# LCD_VGA.net
KiCad netlist of a schematic drawn in Altium Designer
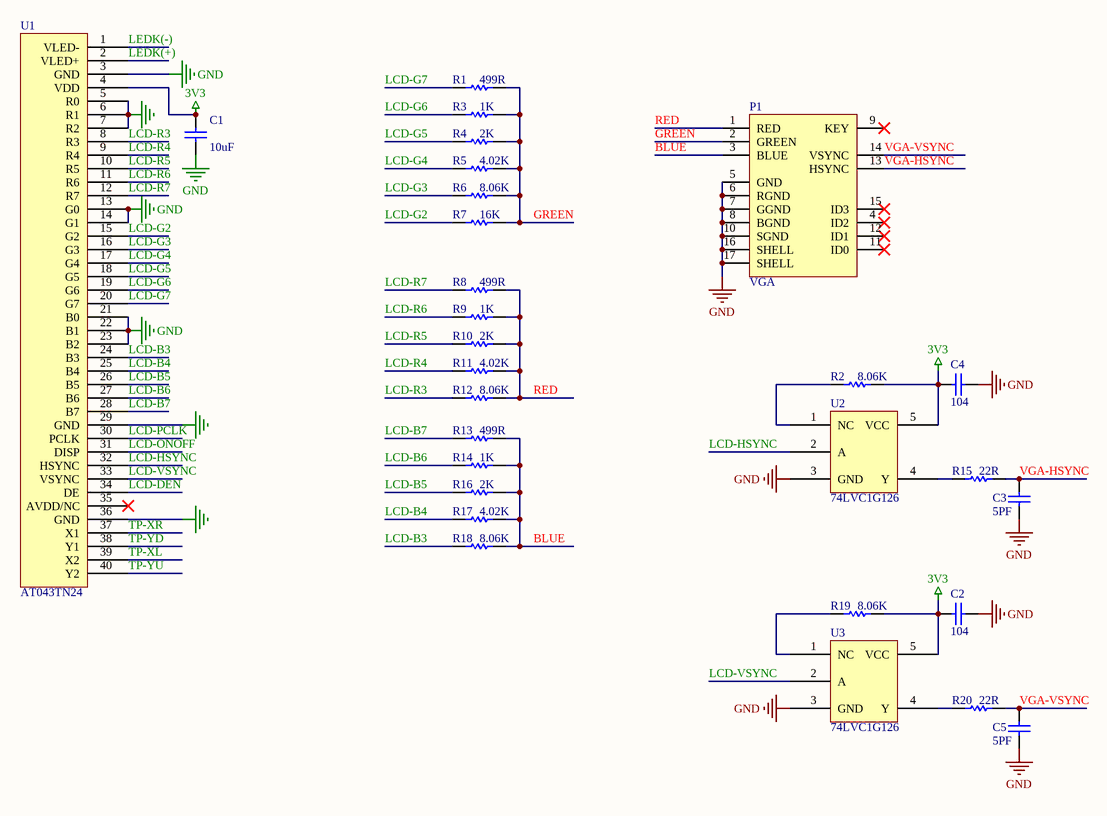
[diagram p0: LCD_VGA.SchDoc]

(export (version "E")
  (design (tool "Eeschema 10.0.6"))
  (components
    (comp (ref "C1")
      (value "C10uF")
      (footprint "0603C")
      (fields (field (name "ALTIUM_UNNAMED_1") "10uF"))
      (libsource (lib "OKmeSchLibrary") (part "C10uF-B"))
    )
    (comp (ref "C2")
      (value "104")
      (footprint "0603C")
      (fields (field (name "ALTIUM_UNNAMED_1") "104"))
      (libsource (lib "OKmeSchLibrary") (part "C10uF-B"))
    )
    (comp (ref "C3")
      (value "5PF")
      (footprint "0603C")
      (fields (field (name "ALTIUM_UNNAMED_1") "5PF"))
      (libsource (lib "OKmeSchLibrary") (part "C10uF-B"))
    )
    (comp (ref "C4")
      (value "104")
      (footprint "0603C")
      (fields (field (name "ALTIUM_UNNAMED_1") "104"))
      (libsource (lib "OKmeSchLibrary") (part "C10uF-B"))
    )
    (comp (ref "C5")
      (value "5PF")
      (footprint "0603C")
      (fields (field (name "ALTIUM_UNNAMED_1") "5PF"))
      (libsource (lib "OKmeSchLibrary") (part "C10uF-B"))
    )
    (comp (ref "P1") (value "VGA") (footprint "VGA-DB15") (libsource (lib "osc_dev") (part "VGA")))
    (comp (ref "R1")
      (value "499R")
      (footprint "0603R")
      (fields (field (name "ALTIUM_UNNAMED_1") "499R"))
      (libsource (lib "OKmeSchLibrary") (part "R1M"))
    )
    (comp (ref "R2")
      (value "8.06K")
      (footprint "0603R")
      (fields (field (name "ALTIUM_UNNAMED_1") "8.06K"))
      (libsource (lib "OKmeSchLibrary") (part "R1M"))
    )
    (comp (ref "R3")
      (value "1K")
      (footprint "0603R")
      (fields (field (name "ALTIUM_UNNAMED_1") "1K"))
      (libsource (lib "OKmeSchLibrary") (part "R1M"))
    )
    (comp (ref "R4")
      (value "2K")
      (footprint "0603R")
      (fields (field (name "ALTIUM_UNNAMED_1") "2K"))
      (libsource (lib "OKmeSchLibrary") (part "R1M"))
    )
    (comp (ref "R5")
      (value "4.02K")
      (footprint "0603R")
      (fields (field (name "ALTIUM_UNNAMED_1") "4.02K"))
      (libsource (lib "OKmeSchLibrary") (part "R1M"))
    )
    (comp (ref "R6")
      (value "8.06K")
      (footprint "0603R")
      (fields (field (name "ALTIUM_UNNAMED_1") "8.06K"))
      (libsource (lib "OKmeSchLibrary") (part "R1M"))
    )
    (comp (ref "R7")
      (value "16K")
      (footprint "0603R")
      (fields (field (name "ALTIUM_UNNAMED_1") "16K"))
      (libsource (lib "OKmeSchLibrary") (part "R1M"))
    )
    (comp (ref "R8")
      (value "499R")
      (footprint "0603R")
      (fields (field (name "ALTIUM_UNNAMED_1") "499R"))
      (libsource (lib "OKmeSchLibrary") (part "R1M"))
    )
    (comp (ref "R9")
      (value "1K")
      (footprint "0603R")
      (fields (field (name "ALTIUM_UNNAMED_1") "1K"))
      (libsource (lib "OKmeSchLibrary") (part "R1M"))
    )
    (comp (ref "R10")
      (value "2K")
      (footprint "0603R")
      (fields (field (name "ALTIUM_UNNAMED_1") "2K"))
      (libsource (lib "OKmeSchLibrary") (part "R1M"))
    )
    (comp (ref "R11")
      (value "4.02K")
      (footprint "0603R")
      (fields (field (name "ALTIUM_UNNAMED_1") "4.02K"))
      (libsource (lib "OKmeSchLibrary") (part "R1M"))
    )
    (comp (ref "R12")
      (value "8.06K")
      (footprint "0603R")
      (fields (field (name "ALTIUM_UNNAMED_1") "8.06K"))
      (libsource (lib "OKmeSchLibrary") (part "R1M"))
    )
    (comp (ref "R13")
      (value "499R")
      (footprint "0603R")
      (fields (field (name "ALTIUM_UNNAMED_1") "499R"))
      (libsource (lib "OKmeSchLibrary") (part "R1M"))
    )
    (comp (ref "R14")
      (value "1K")
      (footprint "0603R")
      (fields (field (name "ALTIUM_UNNAMED_1") "1K"))
      (libsource (lib "OKmeSchLibrary") (part "R1M"))
    )
    (comp (ref "R15")
      (value "22R")
      (footprint "0603R")
      (fields (field (name "ALTIUM_UNNAMED_1") "22R"))
      (libsource (lib "OKmeSchLibrary") (part "R1M"))
    )
    (comp (ref "R16")
      (value "2K")
      (footprint "0603R")
      (fields (field (name "ALTIUM_UNNAMED_1") "2K"))
      (libsource (lib "OKmeSchLibrary") (part "R1M"))
    )
    (comp (ref "R17")
      (value "4.02K")
      (footprint "0603R")
      (fields (field (name "ALTIUM_UNNAMED_1") "4.02K"))
      (libsource (lib "OKmeSchLibrary") (part "R1M"))
    )
    (comp (ref "R18")
      (value "8.06K")
      (footprint "0603R")
      (fields (field (name "ALTIUM_UNNAMED_1") "8.06K"))
      (libsource (lib "OKmeSchLibrary") (part "R1M"))
    )
    (comp (ref "R19")
      (value "8.06K")
      (footprint "0603R")
      (fields (field (name "ALTIUM_UNNAMED_1") "8.06K"))
      (libsource (lib "OKmeSchLibrary") (part "R1M"))
    )
    (comp (ref "R20")
      (value "22R")
      (footprint "0603R")
      (fields (field (name "ALTIUM_UNNAMED_1") "22R"))
      (libsource (lib "OKmeSchLibrary") (part "R1M"))
    )
    (comp (ref "U1")
      (value "AT043TN24")
      (footprint "FPC40-N")
      (libsource (lib "OKmeSchLibrary") (part "AT043TN24"))
    )
    (comp (ref "U2")
      (value "74LVC1G126")
      (footprint "SOT23-5")
      (libsource (lib "OKmeSchLibrary") (part "74LVC1G17"))
    )
    (comp (ref "U3")
      (value "74LVC1G126")
      (footprint "SOT23-5")
      (libsource (lib "OKmeSchLibrary") (part "74LVC1G17"))
    )
  )
  (nets
    (net (code "1") (name "/BLUE") (class "Default")
      (node (ref "P1") (pin "3") (pinfunction "BLUE_3") (pintype "passive"))
      (node (ref "R13") (pin "1") (pinfunction "1_1") (pintype "passive"))
      (node (ref "R14") (pin "1") (pinfunction "1_1") (pintype "passive"))
      (node (ref "R16") (pin "1") (pinfunction "1_1") (pintype "passive"))
      (node (ref "R17") (pin "1") (pinfunction "1_1") (pintype "passive"))
      (node (ref "R18") (pin "1") (pinfunction "1_1") (pintype "passive"))
    )
    (net (code "2") (name "/GREEN") (class "Default")
      (node (ref "P1") (pin "2") (pinfunction "GREEN_2") (pintype "passive"))
      (node (ref "R1") (pin "1") (pinfunction "1_1") (pintype "passive"))
      (node (ref "R3") (pin "1") (pinfunction "1_1") (pintype "passive"))
      (node (ref "R4") (pin "1") (pinfunction "1_1") (pintype "passive"))
      (node (ref "R5") (pin "1") (pinfunction "1_1") (pintype "passive"))
      (node (ref "R6") (pin "1") (pinfunction "1_1") (pintype "passive"))
      (node (ref "R7") (pin "1") (pinfunction "1_1") (pintype "passive"))
    )
    (net (code "3") (name "/LCD-B3") (class "Default")
      (node (ref "R18") (pin "2") (pinfunction "2_2") (pintype "passive"))
      (node (ref "U1") (pin "24") (pinfunction "B3_24") (pintype "passive"))
    )
    (net (code "4") (name "/LCD-B4") (class "Default")
      (node (ref "R17") (pin "2") (pinfunction "2_2") (pintype "passive"))
      (node (ref "U1") (pin "25") (pinfunction "B4_25") (pintype "passive"))
    )
    (net (code "5") (name "/LCD-B5") (class "Default")
      (node (ref "R16") (pin "2") (pinfunction "2_2") (pintype "passive"))
      (node (ref "U1") (pin "26") (pinfunction "B5_26") (pintype "passive"))
    )
    (net (code "6") (name "/LCD-B6") (class "Default")
      (node (ref "R14") (pin "2") (pinfunction "2_2") (pintype "passive"))
      (node (ref "U1") (pin "27") (pinfunction "B6_27") (pintype "passive"))
    )
    (net (code "7") (name "/LCD-B7") (class "Default")
      (node (ref "R13") (pin "2") (pinfunction "2_2") (pintype "passive"))
      (node (ref "U1") (pin "28") (pinfunction "B7_28") (pintype "passive"))
    )
    (net (code "8") (name "/LCD-DEN") (class "Default")
      (node (ref "U1") (pin "34") (pinfunction "DE_34") (pintype "passive"))
    )
    (net (code "9") (name "/LCD-G2") (class "Default")
      (node (ref "R7") (pin "2") (pinfunction "2_2") (pintype "passive"))
      (node (ref "U1") (pin "15") (pinfunction "G2_15") (pintype "passive"))
    )
    (net (code "10") (name "/LCD-G3") (class "Default")
      (node (ref "R6") (pin "2") (pinfunction "2_2") (pintype "passive"))
      (node (ref "U1") (pin "16") (pinfunction "G3_16") (pintype "passive"))
    )
    (net (code "11") (name "/LCD-G4") (class "Default")
      (node (ref "R5") (pin "2") (pinfunction "2_2") (pintype "passive"))
      (node (ref "U1") (pin "17") (pinfunction "G4_17") (pintype "passive"))
    )
    (net (code "12") (name "/LCD-G5") (class "Default")
      (node (ref "R4") (pin "2") (pinfunction "2_2") (pintype "passive"))
      (node (ref "U1") (pin "18") (pinfunction "G5_18") (pintype "passive"))
    )
    (net (code "13") (name "/LCD-G6") (class "Default")
      (node (ref "R3") (pin "2") (pinfunction "2_2") (pintype "passive"))
      (node (ref "U1") (pin "19") (pinfunction "G6_19") (pintype "passive"))
    )
    (net (code "14") (name "/LCD-G7") (class "Default")
      (node (ref "R1") (pin "2") (pinfunction "2_2") (pintype "passive"))
      (node (ref "U1") (pin "20") (pinfunction "G7_20") (pintype "passive"))
    )
    (net (code "15") (name "/LCD-HSYNC") (class "Default")
      (node (ref "U1") (pin "32") (pinfunction "HSYNC_32") (pintype "passive"))
      (node (ref "U2") (pin "2") (pinfunction "A_2") (pintype "passive"))
    )
    (net (code "16") (name "/LCD-ONOFF") (class "Default")
      (node (ref "U1") (pin "31") (pinfunction "DISP_31") (pintype "passive"))
    )
    (net (code "17") (name "/LCD-PCLK") (class "Default")
      (node (ref "U1") (pin "30") (pinfunction "PCLK_30") (pintype "passive"))
    )
    (net (code "18") (name "/LCD-R3") (class "Default")
      (node (ref "R12") (pin "2") (pinfunction "2_2") (pintype "passive"))
      (node (ref "U1") (pin "8") (pinfunction "R3_8") (pintype "passive"))
    )
    (net (code "19") (name "/LCD-R4") (class "Default")
      (node (ref "R11") (pin "2") (pinfunction "2_2") (pintype "passive"))
      (node (ref "U1") (pin "9") (pinfunction "R4_9") (pintype "passive"))
    )
    (net (code "20") (name "/LCD-R5") (class "Default")
      (node (ref "R10") (pin "2") (pinfunction "2_2") (pintype "passive"))
      (node (ref "U1") (pin "10") (pinfunction "R5_10") (pintype "passive"))
    )
    (net (code "21") (name "/LCD-R6") (class "Default")
      (node (ref "R9") (pin "2") (pinfunction "2_2") (pintype "passive"))
      (node (ref "U1") (pin "11") (pinfunction "R6_11") (pintype "passive"))
    )
    (net (code "22") (name "/LCD-R7") (class "Default")
      (node (ref "R8") (pin "2") (pinfunction "2_2") (pintype "passive"))
      (node (ref "U1") (pin "12") (pinfunction "R7_12") (pintype "passive"))
    )
    (net (code "23") (name "/LCD-VSYNC") (class "Default")
      (node (ref "U1") (pin "33") (pinfunction "VSYNC_33") (pintype "passive"))
      (node (ref "U3") (pin "2") (pinfunction "A_2") (pintype "passive"))
    )
    (net (code "24") (name "/LEDK(+)") (class "Default")
      (node (ref "U1") (pin "2") (pinfunction "VLED+_2") (pintype "passive"))
    )
    (net (code "25") (name "/LEDK(-)") (class "Default")
      (node (ref "U1") (pin "1") (pinfunction "VLED-_1") (pintype "passive"))
    )
    (net (code "26") (name "/RED") (class "Default")
      (node (ref "P1") (pin "1") (pinfunction "RED_1") (pintype "passive"))
      (node (ref "R10") (pin "1") (pinfunction "1_1") (pintype "passive"))
      (node (ref "R11") (pin "1") (pinfunction "1_1") (pintype "passive"))
      (node (ref "R12") (pin "1") (pinfunction "1_1") (pintype "passive"))
      (node (ref "R8") (pin "1") (pinfunction "1_1") (pintype "passive"))
      (node (ref "R9") (pin "1") (pinfunction "1_1") (pintype "passive"))
    )
    (net (code "27") (name "/TP-XL") (class "Default")
      (node (ref "U1") (pin "39") (pinfunction "X2_39") (pintype "passive"))
    )
    (net (code "28") (name "/TP-XR") (class "Default")
      (node (ref "U1") (pin "37") (pinfunction "X1_37") (pintype "passive"))
    )
    (net (code "29") (name "/TP-YD") (class "Default")
      (node (ref "U1") (pin "38") (pinfunction "Y1_38") (pintype "passive"))
    )
    (net (code "30") (name "/TP-YU") (class "Default")
      (node (ref "U1") (pin "40") (pinfunction "Y2_40") (pintype "passive"))
    )
    (net (code "31") (name "/VGA-HSYNC") (class "Default")
      (node (ref "C3") (pin "1") (pinfunction "1_1") (pintype "passive"))
      (node (ref "P1") (pin "13") (pinfunction "HSYNC_13") (pintype "passive"))
      (node (ref "R15") (pin "1") (pinfunction "1_1") (pintype "passive"))
    )
    (net (code "32") (name "/VGA-VSYNC") (class "Default")
      (node (ref "C5") (pin "1") (pinfunction "1_1") (pintype "passive"))
      (node (ref "P1") (pin "14") (pinfunction "VSYNC_14") (pintype "passive"))
      (node (ref "R20") (pin "1") (pinfunction "1_1") (pintype "passive"))
    )
    (net (code "33") (name "3V3") (class "Default")
      (node (ref "C1") (pin "1") (pinfunction "1_1") (pintype "passive"))
      (node (ref "C2") (pin "2") (pinfunction "2_2") (pintype "passive"))
      (node (ref "C4") (pin "2") (pinfunction "2_2") (pintype "passive"))
      (node (ref "R19") (pin "1") (pinfunction "1_1") (pintype "passive"))
      (node (ref "R2") (pin "1") (pinfunction "1_1") (pintype "passive"))
      (node (ref "U1") (pin "4") (pinfunction "VDD_4") (pintype "passive"))
      (node (ref "U2") (pin "5") (pinfunction "VCC_5") (pintype "passive"))
      (node (ref "U3") (pin "5") (pinfunction "VCC_5") (pintype "passive"))
    )
    (net (code "34") (name "GND") (class "Default")
      (node (ref "C1") (pin "2") (pinfunction "2_2") (pintype "passive"))
      (node (ref "C2") (pin "1") (pinfunction "1_1") (pintype "passive"))
      (node (ref "C3") (pin "2") (pinfunction "2_2") (pintype "passive"))
      (node (ref "C4") (pin "1") (pinfunction "1_1") (pintype "passive"))
      (node (ref "C5") (pin "2") (pinfunction "2_2") (pintype "passive"))
      (node (ref "P1") (pin "10") (pinfunction "SGND_10") (pintype "passive"))
      (node (ref "P1") (pin "16") (pinfunction "SHELL_16") (pintype "passive"))
      (node (ref "P1") (pin "17") (pinfunction "SHELL_17") (pintype "passive"))
      (node (ref "P1") (pin "5") (pinfunction "GND_5") (pintype "passive"))
      (node (ref "P1") (pin "6") (pinfunction "RGND_6") (pintype "passive"))
      (node (ref "P1") (pin "7") (pinfunction "GGND_7") (pintype "passive"))
      (node (ref "P1") (pin "8") (pinfunction "BGND_8") (pintype "passive"))
      (node (ref "U1") (pin "13") (pinfunction "G0_13") (pintype "passive"))
      (node (ref "U1") (pin "14") (pinfunction "G1_14") (pintype "passive"))
      (node (ref "U1") (pin "21") (pinfunction "B0_21") (pintype "passive"))
      (node (ref "U1") (pin "22") (pinfunction "B1_22") (pintype "passive"))
      (node (ref "U1") (pin "23") (pinfunction "B2_23") (pintype "passive"))
      (node (ref "U1") (pin "29") (pinfunction "GND_29") (pintype "passive"))
      (node (ref "U1") (pin "3") (pinfunction "GND_3") (pintype "passive"))
      (node (ref "U1") (pin "36") (pinfunction "GND_36") (pintype "passive"))
      (node (ref "U1") (pin "5") (pinfunction "R0_5") (pintype "passive"))
      (node (ref "U1") (pin "6") (pinfunction "R1_6") (pintype "passive"))
      (node (ref "U1") (pin "7") (pinfunction "R2_7") (pintype "passive"))
      (node (ref "U2") (pin "3") (pinfunction "GND_3") (pintype "passive"))
      (node (ref "U3") (pin "3") (pinfunction "GND_3") (pintype "passive"))
    )
    (net (code "35") (name "Net-(U2-NC)") (class "Default")
      (node (ref "R2") (pin "2") (pinfunction "2_2") (pintype "passive"))
      (node (ref "U2") (pin "1") (pinfunction "NC_1") (pintype "passive"))
    )
    (net (code "36") (name "Net-(U2-Y)") (class "Default")
      (node (ref "R15") (pin "2") (pinfunction "2_2") (pintype "passive"))
      (node (ref "U2") (pin "4") (pinfunction "Y_4") (pintype "passive"))
    )
    (net (code "37") (name "Net-(U3-NC)") (class "Default")
      (node (ref "R19") (pin "2") (pinfunction "2_2") (pintype "passive"))
      (node (ref "U3") (pin "1") (pinfunction "NC_1") (pintype "passive"))
    )
    (net (code "38") (name "Net-(U3-Y)") (class "Default")
      (node (ref "R20") (pin "2") (pinfunction "2_2") (pintype "passive"))
      (node (ref "U3") (pin "4") (pinfunction "Y_4") (pintype "passive"))
    )
    (net (code "39") (name "unconnected-(P1-ID0-Pad11)") (class "Default")
      (node (ref "P1") (pin "11") (pinfunction "ID0_11") (pintype "passive+no_connect"))
    )
    (net (code "40") (name "unconnected-(P1-ID1-Pad12)") (class "Default")
      (node (ref "P1") (pin "12") (pinfunction "ID1_12") (pintype "passive+no_connect"))
    )
    (net (code "41") (name "unconnected-(P1-ID2-Pad4)") (class "Default")
      (node (ref "P1") (pin "4") (pinfunction "ID2_4") (pintype "passive+no_connect"))
    )
    (net (code "42") (name "unconnected-(P1-ID3-Pad15)") (class "Default")
      (node (ref "P1") (pin "15") (pinfunction "ID3_15") (pintype "passive+no_connect"))
    )
    (net (code "43") (name "unconnected-(P1-KEY-Pad9)") (class "Default")
      (node (ref "P1") (pin "9") (pinfunction "KEY_9") (pintype "passive+no_connect"))
    )
    (net (code "44") (name "unconnected-(U1-AVDD{slash}NC-Pad35)") (class "Default")
      (node (ref "U1") (pin "35") (pinfunction "AVDD/NC_35") (pintype "passive+no_connect"))
    )
  )
)
